# MDL_FUENTE_5V.net
KiCad netlist of a schematic drawn in Altium Designer
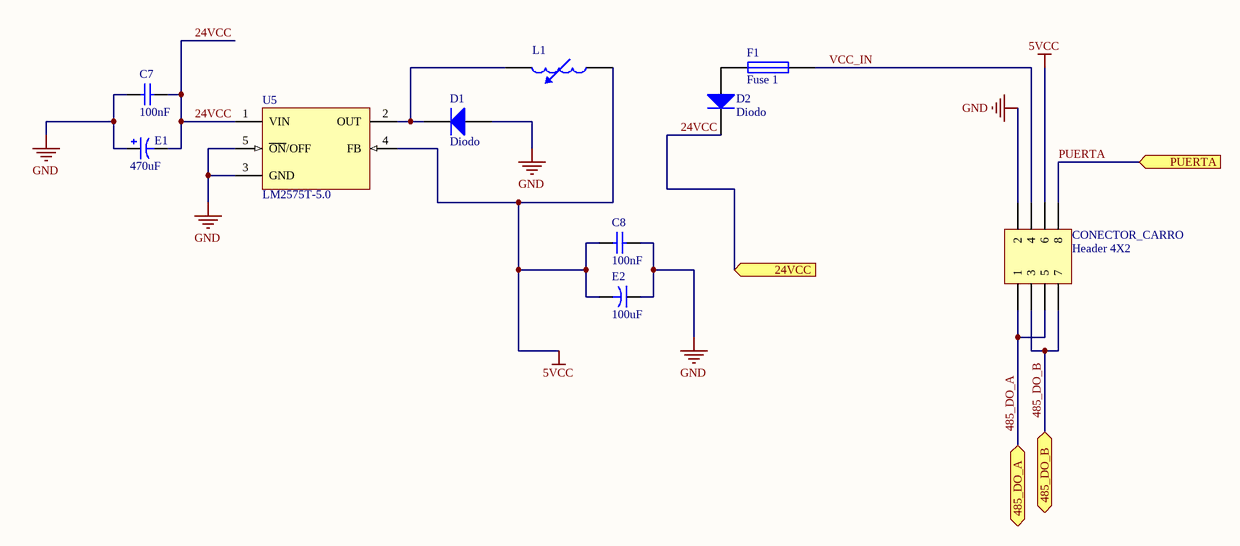
[diagram p0: MDL_FUENTE_5V.SchDoc]

(export (version "E")
  (design (tool "Eeschema 10.0.6"))
  (components
    (comp (ref "C7")
      (value "100nF")
      (footprint "VP44-2.5")
      (description "Dipped Radial Multilayer Ceramic Capacitor X7R: 220nF, 100V")
      (fields (field (name "Comment") "VP44BY224JB") (field (name "PUBLISHER") "Altium Limited"))
      (libsource (lib "Vishay Vitramon Ceramic Dipped Capacitor") (part "VP44BY224JB"))
    )
    (comp (ref "C8")
      (value "100nF")
      (footprint "VP44-2.5")
      (description "Dipped Radial Multilayer Ceramic Capacitor X7R: 220nF, 100V")
      (fields (field (name "Comment") "VP44BY224JB") (field (name "PUBLISHER") "Altium Limited"))
      (libsource (lib "Vishay Vitramon Ceramic Dipped Capacitor") (part "VP44BY224JB"))
    )
    (comp (ref "CONECTOR_CARRO")
      (value "Header 4X2")
      (footprint "FP_CON12PAUTZ")
      (description "Header, 4-Pin, Dual row")
      (fields (field (name "PUBLISHER") "Altium Limited"))
      (libsource (lib "Miscellaneous Connectors") (part "Header 4X2"))
    )
    (comp (ref "D1")
      (value "Diodo")
      (footprint "1N4000")
      (description "Diodo rectificador")
      (libsource (lib "Diodos") (part "Diodo"))
    )
    (comp (ref "D2")
      (value "Diodo")
      (footprint "1N4000")
      (description "Diodo rectificador")
      (libsource (lib "Diodos") (part "Diodo"))
    )
    (comp (ref "E1")
      (value "470uF")
      (footprint "C1000UF")
      (description "Polarized Capacitor (Radial)")
      (fields (field (name "Comment") "Cap Pol1") (field (name "PUBLISHER") "Altium Limited"))
      (libsource (lib "Miscellaneous Devices") (part "Cap Pol1"))
    )
    (comp (ref "E2")
      (value "100uF")
      (footprint "C1UF")
      (description "Capacitor")
      (fields (field (name "Comment") "Cap2") (field (name "PUBLISHER") "Altium Limited"))
      (libsource (lib "Miscellaneous Devices") (part "Cap2"))
    )
    (comp (ref "F1")
      (value "Fuse 1")
      (footprint "FUSIBLE_BUSMATIC")
      (description "Fuse")
      (fields (field (name "PUBLISHER") "Altium Limited"))
      (libsource (lib "Miscellaneous Devices") (part "Fuse 1"))
    )
    (comp (ref "L1")
      (value "Inductor Adj")
      (footprint "Inductor_redondo")
      (description "Adjustable Inductor")
      (fields (field (name "PUBLISHER") "Altium Limited"))
      (libsource (lib "Miscellaneous Devices") (part "Inductor Adj"))
    )
    (comp (ref "U5")
      (value "LM2575T-5.0")
      (footprint "HDR1X5")
      (description "SIMPLE SWITCHER 1A Step-Down Voltage Regulator")
      (fields
        (field (name "MANUFACTURER") "National Semiconductor")
        (field (name "DIGIKEYPARTNUMBER") "LM2575T-5.0-ND")
        (field (name "PUBLISHER") "Altium Limited")
      )
      (libsource (lib "NSC Switcher") (part "LM2575T-5.0"))
    )
  )
  (nets
    (net (code "1") (name "/24VCC") (class "Default")
      (node (ref "C7") (pin "1") (pinfunction "1_1") (pintype "passive"))
      (node (ref "D2") (pin "2") (pinfunction "K_2") (pintype "passive"))
      (node (ref "E1") (pin "2") (pinfunction "2_2") (pintype "passive"))
      (node (ref "U5") (pin "1") (pinfunction "VIN_1") (pintype "power_in"))
    )
    (net (code "2") (name "/485_DO_A") (class "Default")
      (node (ref "CONECTOR_CARRO") (pin "1") (pinfunction "1_1") (pintype "passive"))
      (node (ref "CONECTOR_CARRO") (pin "5") (pinfunction "5_5") (pintype "passive"))
    )
    (net (code "3") (name "/485_DO_B") (class "Default")
      (node (ref "CONECTOR_CARRO") (pin "3") (pinfunction "3_3") (pintype "passive"))
      (node (ref "CONECTOR_CARRO") (pin "7") (pinfunction "7_7") (pintype "passive"))
    )
    (net (code "4") (name "/PUERTA") (class "Default")
      (node (ref "CONECTOR_CARRO") (pin "8") (pinfunction "8_8") (pintype "passive"))
    )
    (net (code "5") (name "/VCC_IN") (class "Default")
      (node (ref "CONECTOR_CARRO") (pin "4") (pinfunction "4_4") (pintype "passive"))
      (node (ref "F1") (pin "2") (pinfunction "2_2") (pintype "passive"))
    )
    (net (code "6") (name "5VCC") (class "Default")
      (node (ref "C8") (pin "2") (pinfunction "2_2") (pintype "passive"))
      (node (ref "CONECTOR_CARRO") (pin "6") (pinfunction "6_6") (pintype "passive"))
      (node (ref "E2") (pin "2") (pinfunction "2_2") (pintype "passive"))
      (node (ref "L1") (pin "1") (pinfunction "1_1") (pintype "passive"))
      (node (ref "U5") (pin "4") (pinfunction "FB_4") (pintype "input"))
    )
    (net (code "7") (name "GND") (class "Default")
      (node (ref "C7") (pin "2") (pinfunction "2_2") (pintype "passive"))
      (node (ref "C8") (pin "1") (pinfunction "1_1") (pintype "passive"))
      (node (ref "CONECTOR_CARRO") (pin "2") (pinfunction "2_2") (pintype "passive"))
      (node (ref "D1") (pin "1") (pinfunction "A_1") (pintype "passive"))
      (node (ref "E1") (pin "1") (pinfunction "1_1") (pintype "passive"))
      (node (ref "E2") (pin "1") (pinfunction "1_1") (pintype "passive"))
      (node (ref "U5") (pin "3") (pinfunction "GND_3") (pintype "power_in"))
      (node (ref "U5") (pin "5") (pinfunction "~{ON}/OFF_5") (pintype "input"))
    )
    (net (code "8") (name "Net-(D1-K)") (class "Default")
      (node (ref "D1") (pin "2") (pinfunction "K_2") (pintype "passive"))
      (node (ref "L1") (pin "2") (pinfunction "2_2") (pintype "passive"))
      (node (ref "U5") (pin "2") (pinfunction "OUT_2") (pintype "power_in"))
    )
    (net (code "9") (name "Net-(D2-A)") (class "Default")
      (node (ref "D2") (pin "1") (pinfunction "A_1") (pintype "passive"))
      (node (ref "F1") (pin "1") (pinfunction "1_1") (pintype "passive"))
    )
  )
)
